# design.net
KiCad netlist of a schematic drawn in Altium Designer
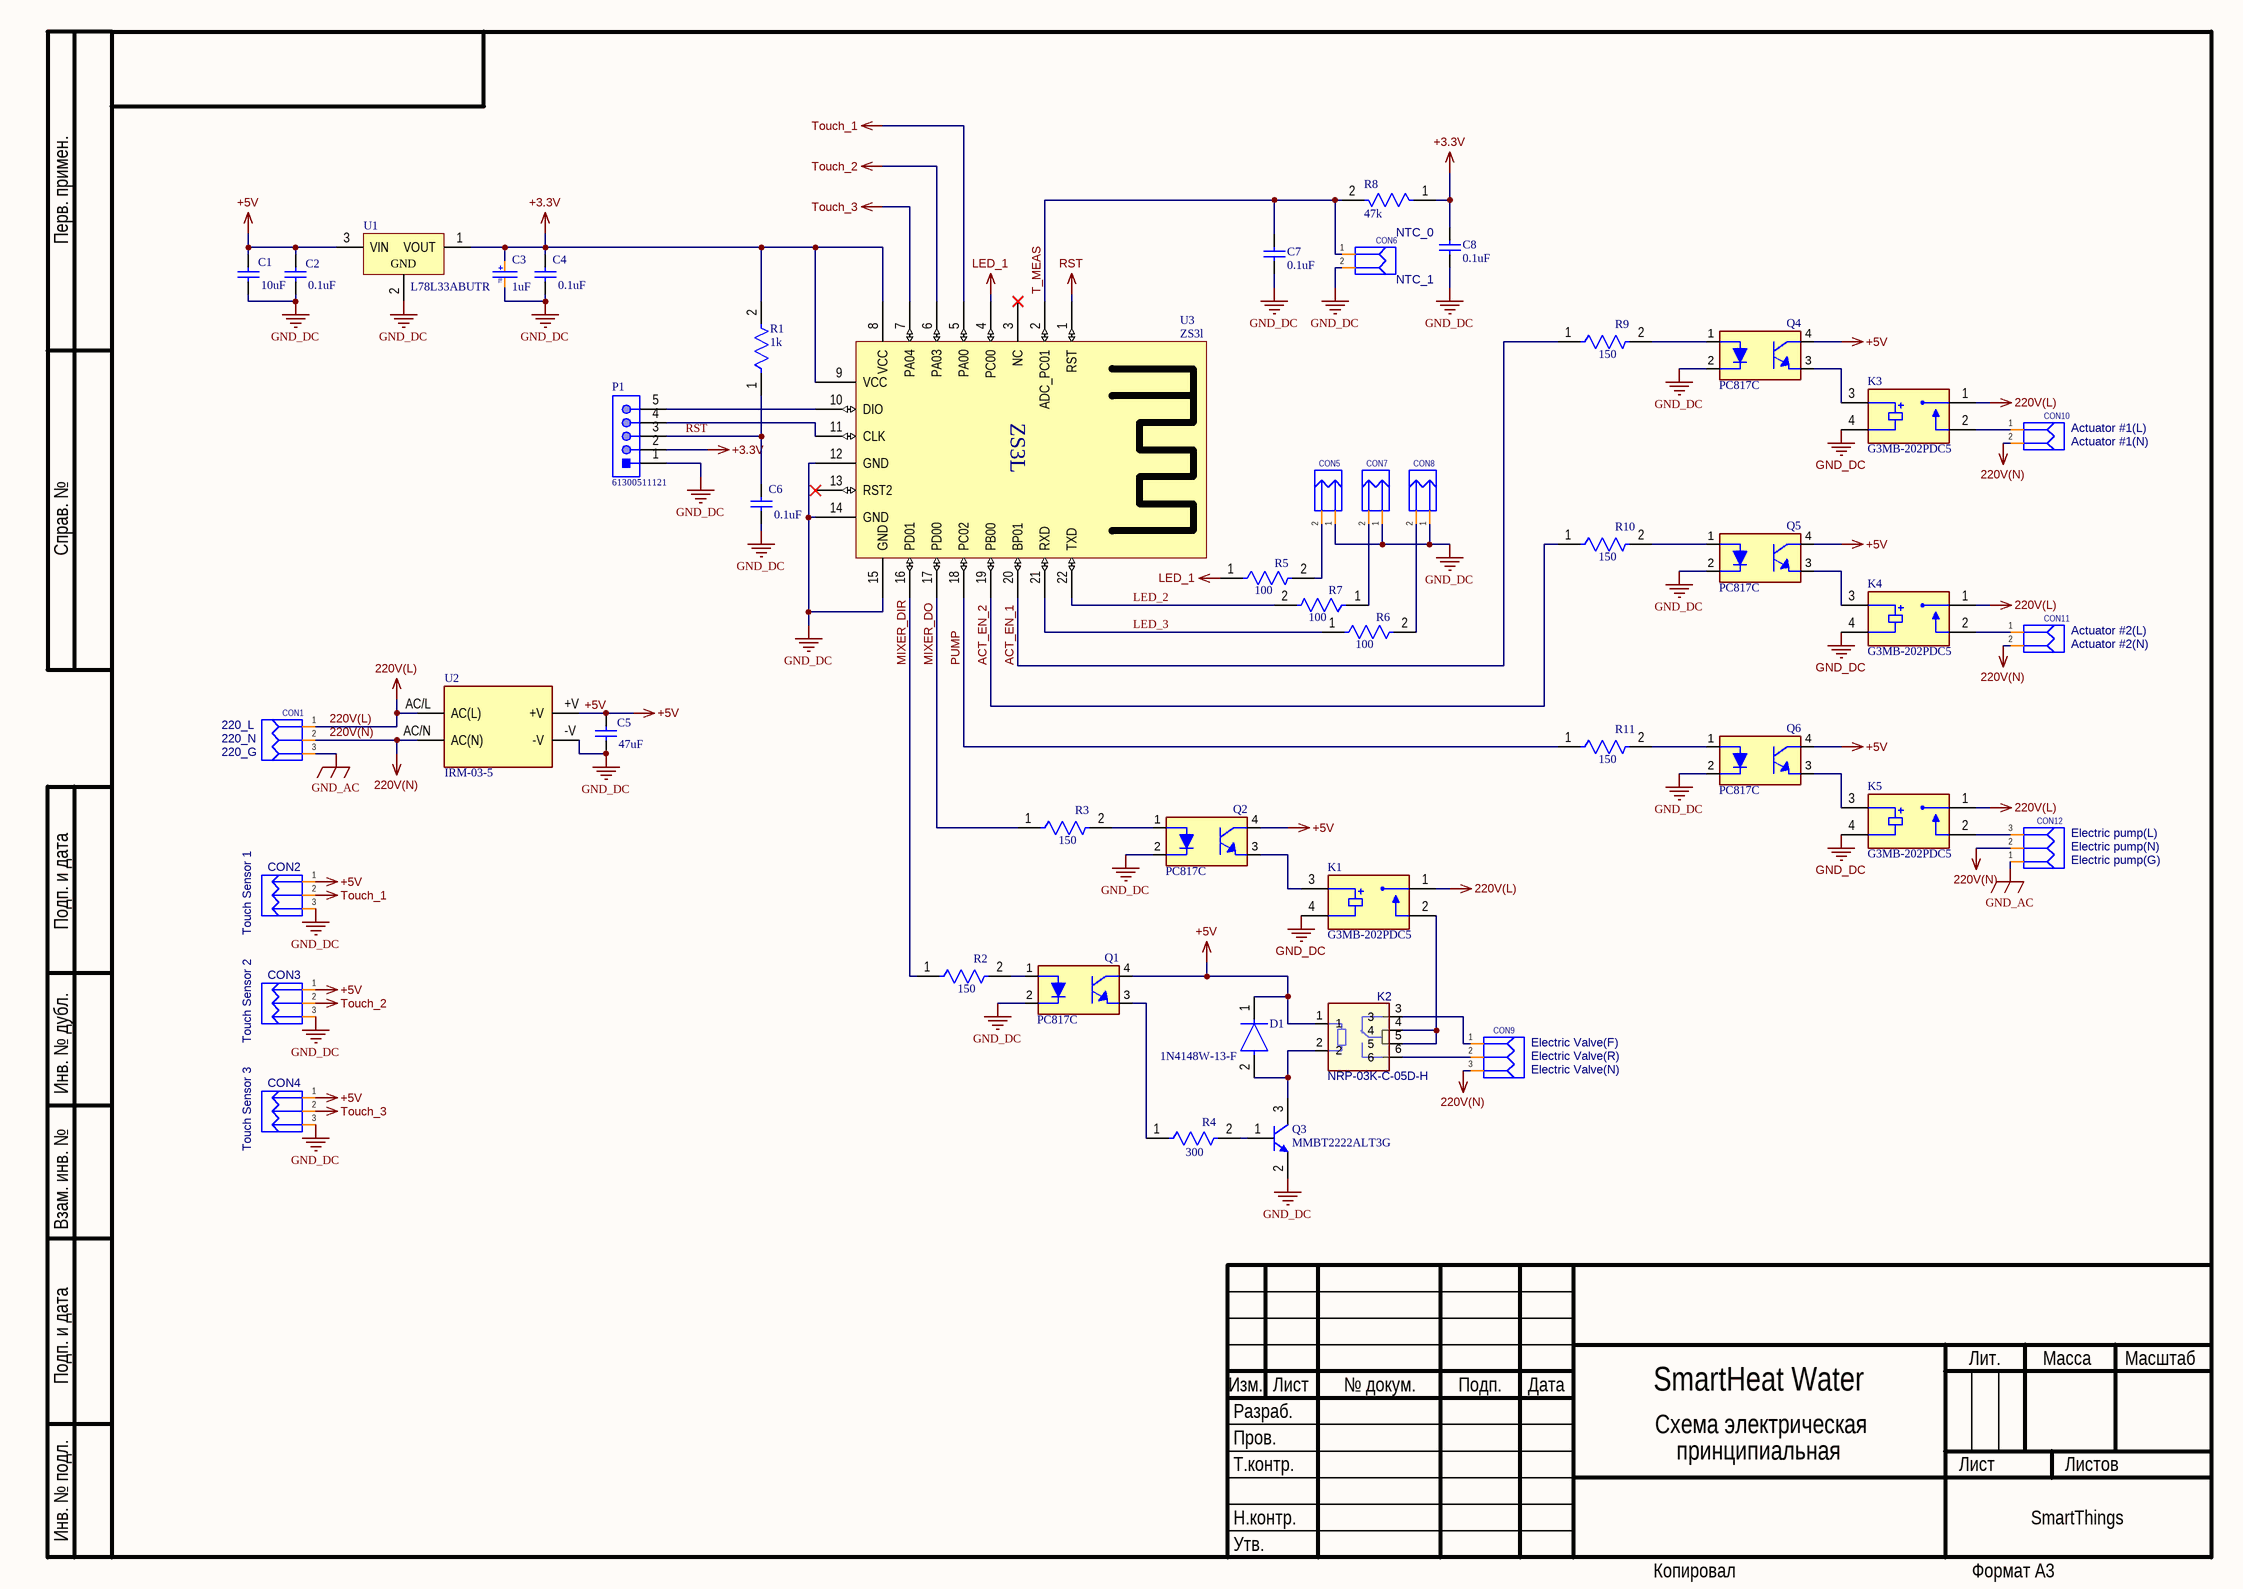
[diagram p0: Схема принципиальная.SchDoc]

(export (version "E")
  (design (tool "Eeschema 10.0.6"))
  (components
    (comp (ref "C1")
      (value "10uF")
      (footprint "CAPC2013X135X45ML10T25")
      (description "GRM21BR61E106KA73L\r\n10uF, +/- 10%, 25 V, 0805")
      (fields (field (name "MANUFACTURER") "Murata"))
      (libsource (lib "Altium Content Vault") (part "CAP-NP-2"))
    )
    (comp (ref "C2")
      (value "0.1uF")
      (footprint "CAPC2013X140X45NL15T25")
      (description "GRM21BR71H104K\r\n0.1 мкФ X7R 10% 50В 0805")
      (fields (field (name "PART NUMBER") "GRM21BR71C475KA73L") (field (name "MANUFACTURER") "Murata"))
      (libsource (lib "Altium Content Vault") (part "CAP"))
    )
    (comp (ref "C3")
      (value "1uF")
      (footprint "TANTAL_B")
      (description "TANTAL TECAP1/50V B, 10%")
      (fields (field (name "PUBLISHER") "Catcatcat Electronics"))
      (libsource (lib "CapacitorElectrolytic") (part "_TANTAL-B"))
    )
    (comp (ref "C4")
      (value "0.1uF")
      (footprint "CAPC2013X140X45NL15T25")
      (description "GRM21BR71H104K\r\n0.1 мкФ X7R 10% 50В 0805")
      (fields (field (name "PART NUMBER") "GRM21BR71C475KA73L") (field (name "MANUFACTURER") "Murata"))
      (libsource (lib "Altium Content Vault") (part "CAP"))
    )
    (comp (ref "C5")
      (value "47uF")
      (footprint "MURA-1210_H_2.7_L")
      (description "Cap Ceramic, 47 uF, +/- 10%, -55 to 85 degC, 2-Pin SMD (1210), RoHS, Tape and Reel")
      (fields (field (name "TOLERANCE") "±10%") (field (name "MANUFACTURER") "Murata"))
      (libsource (lib "Altium Content Vault") (part "CAP-NP-2"))
    )
    (comp (ref "C6")
      (value "0.1uF")
      (footprint "CAPC2013X140X45NL15T25")
      (description "GRM21BR71H104K\r\n0.1 мкФ X7R 10% 50В 0805")
      (fields (field (name "PART NUMBER") "GRM21BR71C475KA73L") (field (name "MANUFACTURER") "Murata"))
      (libsource (lib "Altium Content Vault") (part "CAP"))
    )
    (comp (ref "C7")
      (value "0.1uF")
      (footprint "CAPC2013X140X45NL15T25")
      (description "GRM21BR71H104K\r\n0.1 мкФ X7R 10% 50В 0805")
      (fields (field (name "PART NUMBER") "GRM21BR71C475KA73L") (field (name "MANUFACTURER") "Murata"))
      (libsource (lib "Altium Content Vault") (part "CAP"))
    )
    (comp (ref "C8")
      (value "0.1uF")
      (footprint "CAPC2013X140X45NL15T25")
      (description "GRM21BR71H104K\r\n0.1 мкФ X7R 10% 50В 0805")
      (fields (field (name "PART NUMBER") "GRM21BR71C475KA73L") (field (name "MANUFACTURER") "Murata"))
      (libsource (lib "Altium Content Vault") (part "CAP"))
    )
    (comp (ref "CON1")
      (value "DG129-5.08-3")
      (footprint "DG129-5.08-3")
      (fields (field (name "PUBLISHER") "Catcatcat Electronics"))
      (libsource (lib "Connectors") (part "DG129-5.08-3"))
    )
    (comp (ref "CON2")
      (value "PLS-03")
      (footprint "PLS-03")
      (description "2.54 mm")
      (fields (field (name "PUBLISHER") "Catcatcat Electronics"))
      (libsource (lib "Connectors") (part "PLS-03"))
    )
    (comp (ref "CON3")
      (value "PLS-03")
      (footprint "PLS-03")
      (description "2.54 mm")
      (fields (field (name "PUBLISHER") "Catcatcat Electronics"))
      (libsource (lib "Connectors") (part "PLS-03"))
    )
    (comp (ref "CON4")
      (value "PLS-03")
      (footprint "PLS-03")
      (description "2.54 mm")
      (fields (field (name "PUBLISHER") "Catcatcat Electronics"))
      (libsource (lib "Connectors") (part "PLS-03"))
    )
    (comp (ref "CON5")
      (value "PLS-02")
      (footprint "PLS-02")
      (description "2.54 mm")
      (fields (field (name "PUBLISHER") "Catcatcat Electronics"))
      (libsource (lib "Connectors") (part "PLS-02"))
    )
    (comp (ref "CON6")
      (value "DG129-5.08-2")
      (footprint "DG129-5.08-2")
      (fields (field (name "PUBLISHER") "Catcatcat Electronics"))
      (libsource (lib "Connectors") (part "DG129-5.08-2"))
    )
    (comp (ref "CON7")
      (value "PLS-02")
      (footprint "PLS-02")
      (description "2.54 mm")
      (fields (field (name "PUBLISHER") "Catcatcat Electronics"))
      (libsource (lib "Connectors") (part "PLS-02"))
    )
    (comp (ref "CON8")
      (value "PLS-02")
      (footprint "PLS-02")
      (description "2.54 mm")
      (fields (field (name "PUBLISHER") "Catcatcat Electronics"))
      (libsource (lib "Connectors") (part "PLS-02"))
    )
    (comp (ref "CON9")
      (value "DG129-5.08-3")
      (footprint "DG129-5.08-3")
      (fields (field (name "PUBLISHER") "Catcatcat Electronics"))
      (libsource (lib "Connectors") (part "DG129-5.08-3"))
    )
    (comp (ref "CON10")
      (value "DG129-5.08-2")
      (footprint "DG129-5.08-2")
      (fields (field (name "PUBLISHER") "Catcatcat Electronics"))
      (libsource (lib "Connectors") (part "DG129-5.08-2"))
    )
    (comp (ref "CON11")
      (value "DG129-5.08-2")
      (footprint "DG129-5.08-2")
      (fields (field (name "PUBLISHER") "Catcatcat Electronics"))
      (libsource (lib "Connectors") (part "DG129-5.08-2"))
    )
    (comp (ref "CON12")
      (value "DG129-5.08-3")
      (footprint "DG129-5.08-3")
      (fields (field (name "PUBLISHER") "Catcatcat Electronics"))
      (libsource (lib "Connectors") (part "DG129-5.08-3"))
    )
    (comp (ref "D1")
      (value "1N4148W-13-F")
      (footprint "FP-SOD123-MFG")
      (description "DIODE GEN PURP 100V 150MA SOD123")
      (fields
        (field (name "OCTOPART") "https://octopart.com/1n4148w-13-f-diodes+inc.-2359612")
        (field (name "MANUFACTURER") "Diodes Inc.")
      )
      (libsource (lib "Altium Content Vault") (part "d7152d700b627762746794eb795d46e"))
    )
    (comp (ref "K1")
      (value "G3MB-202PDC5")
      (footprint "G3MB202PDC5:RELAY_G3MB-202PDC5")
      (fields (field (name "MF") "{'manufacturer': u'Omron Automation'}"))
      (libsource (lib "G3MB202PDC5") (part "G3MB-202PDC5"))
    )
    (comp (ref "K2")
      (value "NRP-03K-C-05D-H")
      (footprint "NRP-03K-C-05D-H")
      (libsource (lib "NRP-03K-C-05D-H") (part "NRP-03K-C-05D-H"))
    )
    (comp (ref "K3")
      (value "G3MB-202PDC5")
      (footprint "G3MB202PDC5:RELAY_G3MB-202PDC5")
      (fields (field (name "MF") "{'manufacturer': u'Omron Automation'}"))
      (libsource (lib "G3MB202PDC5") (part "G3MB-202PDC5"))
    )
    (comp (ref "K4")
      (value "G3MB-202PDC5")
      (footprint "G3MB202PDC5:RELAY_G3MB-202PDC5")
      (fields (field (name "MF") "{'manufacturer': u'Omron Automation'}"))
      (libsource (lib "G3MB202PDC5") (part "G3MB-202PDC5"))
    )
    (comp (ref "K5")
      (value "G3MB-202PDC5")
      (footprint "G3MB202PDC5:RELAY_G3MB-202PDC5")
      (fields (field (name "MF") "{'manufacturer': u'Omron Automation'}"))
      (libsource (lib "G3MB202PDC5") (part "G3MB-202PDC5"))
    )
    (comp (ref "P1")
      (value "61300511121")
      (footprint "61300511121")
      (description "THT Vertical Pin Header WR-PHD, Pitch 2.54 mm, Single Row, 5 pins")
      (fields (field (name "MANUFACTURER") "Wurth Elektronik") (field (name "PUBLISHER") "WurthElektronik"))
      (libsource (lib "5pin_conn") (part "CMP-1502-01068-1"))
    )
    (comp (ref "Q1")
      (value "PC817C")
      (footprint "PC817C:DIP762W50P254L650H458Q4B")
      (description "High Density Mounting Type Photocoupler")
      (fields (field (name "MF") "{'manufacturer': u'Taiwan Semiconductor'}"))
      (libsource (lib "PC817C") (part "PC817C"))
    )
    (comp (ref "Q2")
      (value "PC817C")
      (footprint "PC817C:DIP762W50P254L650H458Q4B")
      (description "High Density Mounting Type Photocoupler")
      (fields (field (name "MF") "{'manufacturer': u'Taiwan Semiconductor'}"))
      (libsource (lib "PC817C") (part "PC817C"))
    )
    (comp (ref "Q3")
      (value "MMBT2222ALT3G")
      (footprint "ONSC-SOT-23-3-318-08_V")
      (description "General Purpose Transistor, NPN Silicon, 3-Pin SOT-23, Pb-Free, Tape and Reel")
      (fields (field (name "MANUFACTURER") "On Semiconductor"))
      (libsource (lib "Altium Content Vault") (part "ONSC-NPN-B1E2C3-3"))
    )
    (comp (ref "Q4")
      (value "PC817C")
      (footprint "PC817C:DIP762W50P254L650H458Q4B")
      (description "High Density Mounting Type Photocoupler")
      (fields (field (name "MF") "{'manufacturer': u'Taiwan Semiconductor'}"))
      (libsource (lib "PC817C") (part "PC817C"))
    )
    (comp (ref "Q5")
      (value "PC817C")
      (footprint "PC817C:DIP762W50P254L650H458Q4B")
      (description "High Density Mounting Type Photocoupler")
      (fields (field (name "MF") "{'manufacturer': u'Taiwan Semiconductor'}"))
      (libsource (lib "PC817C") (part "PC817C"))
    )
    (comp (ref "Q6")
      (value "PC817C")
      (footprint "PC817C:DIP762W50P254L650H458Q4B")
      (description "High Density Mounting Type Photocoupler")
      (fields (field (name "MF") "{'manufacturer': u'Taiwan Semiconductor'}"))
      (libsource (lib "PC817C") (part "PC817C"))
    )
    (comp (ref "R1")
      (value "1k")
      (footprint "FP-CR0805-IPC_C")
      (description "0805 150Ω 0.125W 1%")
      (fields (field (name "TOLERANCE") "1%"))
      (libsource (lib "Altium Content Vault") (part "1029c3af85768c4190bb7ad29bc67b5"))
    )
    (comp (ref "R2")
      (value "150")
      (footprint "FP-CR0805-IPC_C")
      (description "0805 150Ω 0.125W 1%")
      (fields (field (name "TOLERANCE") "1%"))
      (libsource (lib "Altium Content Vault") (part "1029c3af85768c4190bb7ad29bc67b5"))
    )
    (comp (ref "R3")
      (value "150")
      (footprint "FP-CR0805-IPC_C")
      (description "0805 150Ω 0.125W 1%")
      (fields (field (name "TOLERANCE") "1%"))
      (libsource (lib "Altium Content Vault") (part "1029c3af85768c4190bb7ad29bc67b5"))
    )
    (comp (ref "R4")
      (value "300")
      (footprint "FP-CR0805-IPC_C")
      (description "0805 300kΩ 0.125W 1%")
      (fields (field (name "TOLERANCE") "1%"))
      (libsource (lib "Altium Content Vault") (part "1029c3af85768c4190bb7ad29bc67b5"))
    )
    (comp (ref "R5")
      (value "100")
      (footprint "FP-CR0805-IPC_C")
      (description "0805 150Ω 0.125W 1%")
      (fields (field (name "TOLERANCE") "1%"))
      (libsource (lib "Altium Content Vault") (part "1029c3af85768c4190bb7ad29bc67b5"))
    )
    (comp (ref "R6")
      (value "100")
      (footprint "FP-CR0805-IPC_C")
      (description "0805 150Ω 0.125W 1%")
      (fields (field (name "TOLERANCE") "1%"))
      (libsource (lib "Altium Content Vault") (part "1029c3af85768c4190bb7ad29bc67b5"))
    )
    (comp (ref "R7")
      (value "100")
      (footprint "FP-CR0805-IPC_C")
      (description "0805 150Ω 0.125W 1%")
      (fields (field (name "TOLERANCE") "1%"))
      (libsource (lib "Altium Content Vault") (part "1029c3af85768c4190bb7ad29bc67b5"))
    )
    (comp (ref "R8")
      (value "47k")
      (footprint "FP-CRCW1206-e3-IPC_C")
      (description "10kΩ, 1%, 0.25W 1206")
      (fields (field (name "TOLERANCE") "1%"))
      (libsource (lib "Altium Content Vault") (part "1029c3af85768c4190bb7ad29bc67b5"))
    )
    (comp (ref "R9")
      (value "150")
      (footprint "FP-CR0805-IPC_C")
      (description "0805 150Ω 0.125W 1%")
      (fields (field (name "TOLERANCE") "1%"))
      (libsource (lib "Altium Content Vault") (part "1029c3af85768c4190bb7ad29bc67b5"))
    )
    (comp (ref "R10")
      (value "150")
      (footprint "FP-CR0805-IPC_C")
      (description "0805 150Ω 0.125W 1%")
      (fields (field (name "TOLERANCE") "1%"))
      (libsource (lib "Altium Content Vault") (part "1029c3af85768c4190bb7ad29bc67b5"))
    )
    (comp (ref "R11")
      (value "150")
      (footprint "FP-CR0805-IPC_C")
      (description "0805 150Ω 0.125W 1%")
      (fields (field (name "TOLERANCE") "1%"))
      (libsource (lib "Altium Content Vault") (part "1029c3af85768c4190bb7ad29bc67b5"))
    )
    (comp (ref "U1")
      (value "L78L33ABUTR")
      (footprint "SOT-89_L")
      (libsource (lib "L78L33ABUTR") (part "CMP-0244-00410-1"))
    )
    (comp (ref "U2")
      (value "IRM-03-5")
      (footprint "footprint_IRM-03-5")
      (description "AC-DC Single output Encapsulated power supply; Output 5Vdc at 0.6A; PCB mount, miniature size")
      (fields (field (name "MF") "{'manufacturer': u'MEAN WELL'}"))
      (libsource (lib "IRM-03-5") (part "IRM-03-5"))
    )
    (comp (ref "U3")
      (value "ZS3l")
      (footprint "zs3l")
      (description "ZS3L module on chip EFR32MG21A020F768IM32")
      (libsource (lib "zs3l") (part "ZS3l"))
    )
  )
  (nets
    (net (code "1") (name "+3.3V") (class "Default")
      (node (ref "C3") (pin "1") (pintype "passive"))
      (node (ref "C4") (pin "2") (pinfunction "2_2") (pintype "passive"))
      (node (ref "C8") (pin "2") (pinfunction "2_2") (pintype "passive"))
      (node (ref "P1") (pin "2") (pinfunction "2_2") (pintype "passive"))
      (node (ref "R1") (pin "2") (pinfunction "2_2") (pintype "passive"))
      (node (ref "R8") (pin "1") (pinfunction "1_1") (pintype "passive"))
      (node (ref "U1") (pin "1") (pinfunction "VOUT_1") (pintype "power_in"))
      (node (ref "U3") (pin "8") (pinfunction "VCC_8") (pintype "power_in"))
      (node (ref "U3") (pin "9") (pinfunction "VCC_9") (pintype "power_in"))
    )
    (net (code "2") (name "+5V") (class "Default")
      (node (ref "C1") (pin "2") (pinfunction "2_2") (pintype "passive"))
      (node (ref "C2") (pin "2") (pinfunction "2_2") (pintype "passive"))
      (node (ref "C5") (pin "2") (pinfunction "2_2") (pintype "passive"))
      (node (ref "CON2") (pin "1") (pinfunction "1_1") (pintype "passive"))
      (node (ref "CON3") (pin "1") (pinfunction "1_1") (pintype "passive"))
      (node (ref "CON4") (pin "1") (pinfunction "1_1") (pintype "passive"))
      (node (ref "D1") (pin "1") (pinfunction "C_1") (pintype "passive"))
      (node (ref "K2") (pin "1") (pinfunction "1_1") (pintype "passive"))
      (node (ref "Q1") (pin "4") (pinfunction "4_4") (pintype "passive"))
      (node (ref "Q2") (pin "4") (pinfunction "4_4") (pintype "passive"))
      (node (ref "Q4") (pin "4") (pinfunction "4_4") (pintype "passive"))
      (node (ref "Q5") (pin "4") (pinfunction "4_4") (pintype "passive"))
      (node (ref "Q6") (pin "4") (pinfunction "4_4") (pintype "passive"))
      (node (ref "U1") (pin "3") (pinfunction "VIN_3") (pintype "power_in"))
      (node (ref "U2") (pin "+V") (pinfunction "+V_+V") (pintype "power_in"))
    )
    (net (code "3") (name "/ACT_EN_1") (class "Default")
      (node (ref "R9") (pin "1") (pinfunction "1_1") (pintype "passive"))
      (node (ref "U3") (pin "20") (pinfunction "BP01_20") (pintype "bidirectional"))
    )
    (net (code "4") (name "/ACT_EN_2") (class "Default")
      (node (ref "R10") (pin "1") (pinfunction "1_1") (pintype "passive"))
      (node (ref "U3") (pin "19") (pinfunction "PB00_19") (pintype "bidirectional"))
    )
    (net (code "5") (name "/LED_2") (class "Default")
      (node (ref "R7") (pin "2") (pinfunction "2_2") (pintype "passive"))
      (node (ref "U3") (pin "22") (pinfunction "TXD_22") (pintype "bidirectional"))
    )
    (net (code "6") (name "/LED_3") (class "Default")
      (node (ref "R6") (pin "1") (pinfunction "1_1") (pintype "passive"))
      (node (ref "U3") (pin "21") (pinfunction "RXD_21") (pintype "bidirectional"))
    )
    (net (code "7") (name "/MIXER_DIR") (class "Default")
      (node (ref "R2") (pin "1") (pinfunction "1_1") (pintype "passive"))
      (node (ref "U3") (pin "16") (pinfunction "PD01_16") (pintype "bidirectional"))
    )
    (net (code "8") (name "/MIXER_DO") (class "Default")
      (node (ref "R3") (pin "1") (pinfunction "1_1") (pintype "passive"))
      (node (ref "U3") (pin "17") (pinfunction "PD00_17") (pintype "bidirectional"))
    )
    (net (code "9") (name "/PUMP") (class "Default")
      (node (ref "R11") (pin "1") (pinfunction "1_1") (pintype "passive"))
      (node (ref "U3") (pin "18") (pinfunction "PC02_18") (pintype "bidirectional"))
    )
    (net (code "10") (name "/T_MEAS") (class "Default")
      (node (ref "C7") (pin "2") (pinfunction "2_2") (pintype "passive"))
      (node (ref "CON6") (pin "1") (pinfunction "1_1") (pintype "passive"))
      (node (ref "R8") (pin "2") (pinfunction "2_2") (pintype "passive"))
      (node (ref "U3") (pin "2") (pinfunction "ADC_PC01_2") (pintype "bidirectional"))
    )
    (net (code "11") (name "220V(L)") (class "Default")
      (node (ref "CON1") (pin "1") (pinfunction "1_1") (pintype "passive"))
      (node (ref "K1") (pin "1") (pinfunction "1_1") (pintype "passive"))
      (node (ref "K3") (pin "1") (pinfunction "1_1") (pintype "passive"))
      (node (ref "K4") (pin "1") (pinfunction "1_1") (pintype "passive"))
      (node (ref "K5") (pin "1") (pinfunction "1_1") (pintype "passive"))
      (node (ref "U2") (pin "AC/L") (pinfunction "AC(L)_AC/L") (pintype "power_in"))
    )
    (net (code "12") (name "220V(N)") (class "Default")
      (node (ref "CON1") (pin "2") (pinfunction "2_2") (pintype "passive"))
      (node (ref "CON10") (pin "2") (pinfunction "2_2") (pintype "passive"))
      (node (ref "CON11") (pin "2") (pinfunction "2_2") (pintype "passive"))
      (node (ref "CON12") (pin "2") (pinfunction "2_2") (pintype "passive"))
      (node (ref "CON9") (pin "3") (pinfunction "3_3") (pintype "passive"))
      (node (ref "U2") (pin "AC/N") (pinfunction "AC(N)_AC/N") (pintype "power_in"))
    )
    (net (code "13") (name "GND_AC") (class "Default")
      (node (ref "CON1") (pin "3") (pinfunction "3_3") (pintype "passive"))
      (node (ref "CON12") (pin "1") (pinfunction "1_1") (pintype "passive"))
    )
    (net (code "14") (name "GND_DC") (class "Default")
      (node (ref "C1") (pin "1") (pinfunction "1_1") (pintype "passive"))
      (node (ref "C2") (pin "1") (pinfunction "1_1") (pintype "passive"))
      (node (ref "C3") (pin "2") (pintype "passive"))
      (node (ref "C4") (pin "1") (pinfunction "1_1") (pintype "passive"))
      (node (ref "C5") (pin "1") (pinfunction "1_1") (pintype "passive"))
      (node (ref "C6") (pin "1") (pinfunction "1_1") (pintype "passive"))
      (node (ref "C7") (pin "1") (pinfunction "1_1") (pintype "passive"))
      (node (ref "C8") (pin "1") (pinfunction "1_1") (pintype "passive"))
      (node (ref "CON2") (pin "3") (pinfunction "3_3") (pintype "passive"))
      (node (ref "CON3") (pin "3") (pinfunction "3_3") (pintype "passive"))
      (node (ref "CON4") (pin "3") (pinfunction "3_3") (pintype "passive"))
      (node (ref "CON5") (pin "1") (pinfunction "1_1") (pintype "passive"))
      (node (ref "CON6") (pin "2") (pinfunction "2_2") (pintype "passive"))
      (node (ref "CON7") (pin "1") (pinfunction "1_1") (pintype "passive"))
      (node (ref "CON8") (pin "1") (pinfunction "1_1") (pintype "passive"))
      (node (ref "K1") (pin "4") (pinfunction "4_4") (pintype "passive"))
      (node (ref "K3") (pin "4") (pinfunction "4_4") (pintype "passive"))
      (node (ref "K4") (pin "4") (pinfunction "4_4") (pintype "passive"))
      (node (ref "K5") (pin "4") (pinfunction "4_4") (pintype "passive"))
      (node (ref "P1") (pin "1") (pinfunction "1_1") (pintype "passive"))
      (node (ref "Q1") (pin "2") (pinfunction "2_2") (pintype "passive"))
      (node (ref "Q2") (pin "2") (pinfunction "2_2") (pintype "passive"))
      (node (ref "Q3") (pin "2") (pinfunction "E_2") (pintype "passive"))
      (node (ref "Q4") (pin "2") (pinfunction "2_2") (pintype "passive"))
      (node (ref "Q5") (pin "2") (pinfunction "2_2") (pintype "passive"))
      (node (ref "Q6") (pin "2") (pinfunction "2_2") (pintype "passive"))
      (node (ref "U1") (pin "2") (pinfunction "GND_2") (pintype "power_in"))
      (node (ref "U2") (pin "-V") (pinfunction "-V_-V") (pintype "power_in"))
      (node (ref "U3") (pin "12") (pinfunction "GND_12") (pintype "power_in"))
      (node (ref "U3") (pin "14") (pinfunction "GND_14") (pintype "power_in"))
      (node (ref "U3") (pin "15") (pinfunction "GND_15") (pintype "power_in"))
    )
    (net (code "15") (name "LED_1") (class "Default")
      (node (ref "R5") (pin "1") (pinfunction "1_1") (pintype "passive"))
      (node (ref "U3") (pin "4") (pinfunction "PC00_4") (pintype "bidirectional"))
    )
    (net (code "16") (name "Net-(CON5-Pad2)") (class "Default")
      (node (ref "CON5") (pin "2") (pinfunction "2_2") (pintype "passive"))
      (node (ref "R5") (pin "2") (pinfunction "2_2") (pintype "passive"))
    )
    (net (code "17") (name "Net-(CON7-Pad2)") (class "Default")
      (node (ref "CON7") (pin "2") (pinfunction "2_2") (pintype "passive"))
      (node (ref "R7") (pin "1") (pinfunction "1_1") (pintype "passive"))
    )
    (net (code "18") (name "Net-(CON8-Pad2)") (class "Default")
      (node (ref "CON8") (pin "2") (pinfunction "2_2") (pintype "passive"))
      (node (ref "R6") (pin "2") (pinfunction "2_2") (pintype "passive"))
    )
    (net (code "19") (name "Net-(CON9-Pad1)") (class "Default")
      (node (ref "CON9") (pin "1") (pinfunction "1_1") (pintype "passive"))
      (node (ref "K2") (pin "3") (pinfunction "3_3") (pintype "passive"))
    )
    (net (code "20") (name "Net-(CON9-Pad2)") (class "Default")
      (node (ref "CON9") (pin "2") (pinfunction "2_2") (pintype "passive"))
      (node (ref "K2") (pin "6") (pinfunction "6_6") (pintype "passive"))
    )
    (net (code "21") (name "Net-(CON10-Pad1)") (class "Default")
      (node (ref "CON10") (pin "1") (pinfunction "1_1") (pintype "passive"))
      (node (ref "K3") (pin "2") (pinfunction "2_2") (pintype "passive"))
    )
    (net (code "22") (name "Net-(CON11-Pad1)") (class "Default")
      (node (ref "CON11") (pin "1") (pinfunction "1_1") (pintype "passive"))
      (node (ref "K4") (pin "2") (pinfunction "2_2") (pintype "passive"))
    )
    (net (code "23") (name "Net-(CON12-Pad3)") (class "Default")
      (node (ref "CON12") (pin "3") (pinfunction "3_3") (pintype "passive"))
      (node (ref "K5") (pin "2") (pinfunction "2_2") (pintype "passive"))
    )
    (net (code "24") (name "Net-(D1-A)") (class "Default")
      (node (ref "D1") (pin "2") (pinfunction "A_2") (pintype "passive"))
      (node (ref "K2") (pin "2") (pinfunction "2_2") (pintype "passive"))
      (node (ref "Q3") (pin "3") (pinfunction "C_3") (pintype "passive"))
    )
    (net (code "25") (name "Net-(K1-Pad2)") (class "Default")
      (node (ref "K1") (pin "2") (pinfunction "2_2") (pintype "passive"))
      (node (ref "K2") (pin "4") (pinfunction "4_4") (pintype "passive"))
      (node (ref "K2") (pin "5") (pinfunction "5_5") (pintype "passive"))
    )
    (net (code "26") (name "Net-(K1-Pad3)") (class "Default")
      (node (ref "K1") (pin "3") (pinfunction "3_3") (pintype "passive"))
      (node (ref "Q2") (pin "3") (pinfunction "3_3") (pintype "passive"))
    )
    (net (code "27") (name "Net-(K3-Pad3)") (class "Default")
      (node (ref "K3") (pin "3") (pinfunction "3_3") (pintype "passive"))
      (node (ref "Q4") (pin "3") (pinfunction "3_3") (pintype "passive"))
    )
    (net (code "28") (name "Net-(K4-Pad3)") (class "Default")
      (node (ref "K4") (pin "3") (pinfunction "3_3") (pintype "passive"))
      (node (ref "Q5") (pin "3") (pinfunction "3_3") (pintype "passive"))
    )
    (net (code "29") (name "Net-(K5-Pad3)") (class "Default")
      (node (ref "K5") (pin "3") (pinfunction "3_3") (pintype "passive"))
      (node (ref "Q6") (pin "3") (pinfunction "3_3") (pintype "passive"))
    )
    (net (code "30") (name "Net-(Q1-Pad1)") (class "Default")
      (node (ref "Q1") (pin "1") (pinfunction "1_1") (pintype "passive"))
      (node (ref "R2") (pin "2") (pinfunction "2_2") (pintype "passive"))
    )
    (net (code "31") (name "Net-(Q1-Pad3)") (class "Default")
      (node (ref "Q1") (pin "3") (pinfunction "3_3") (pintype "passive"))
      (node (ref "R4") (pin "1") (pinfunction "1_1") (pintype "passive"))
    )
    (net (code "32") (name "Net-(Q2-Pad1)") (class "Default")
      (node (ref "Q2") (pin "1") (pinfunction "1_1") (pintype "passive"))
      (node (ref "R3") (pin "2") (pinfunction "2_2") (pintype "passive"))
    )
    (net (code "33") (name "Net-(Q3-B)") (class "Default")
      (node (ref "Q3") (pin "1") (pinfunction "B_1") (pintype "passive"))
      (node (ref "R4") (pin "2") (pinfunction "2_2") (pintype "passive"))
    )
    (net (code "34") (name "Net-(Q4-Pad1)") (class "Default")
      (node (ref "Q4") (pin "1") (pinfunction "1_1") (pintype "passive"))
      (node (ref "R9") (pin "2") (pinfunction "2_2") (pintype "passive"))
    )
    (net (code "35") (name "Net-(Q5-Pad1)") (class "Default")
      (node (ref "Q5") (pin "1") (pinfunction "1_1") (pintype "passive"))
      (node (ref "R10") (pin "2") (pinfunction "2_2") (pintype "passive"))
    )
    (net (code "36") (name "Net-(Q6-Pad1)") (class "Default")
      (node (ref "Q6") (pin "1") (pinfunction "1_1") (pintype "passive"))
      (node (ref "R11") (pin "2") (pinfunction "2_2") (pintype "passive"))
    )
    (net (code "37") (name "Net-(U3-CLK)") (class "Default")
      (node (ref "P1") (pin "4") (pinfunction "4_4") (pintype "passive"))
      (node (ref "U3") (pin "11") (pinfunction "CLK_11") (pintype "bidirectional"))
    )
    (net (code "38") (name "Net-(U3-DIO)") (class "Default")
      (node (ref "P1") (pin "5") (pinfunction "5_5") (pintype "passive"))
      (node (ref "U3") (pin "10") (pinfunction "DIO_10") (pintype "bidirectional"))
    )
    (net (code "39") (name "RST") (class "Default")
      (node (ref "C6") (pin "2") (pinfunction "2_2") (pintype "passive"))
      (node (ref "P1") (pin "3") (pinfunction "3_3") (pintype "passive"))
      (node (ref "R1") (pin "1") (pinfunction "1_1") (pintype "passive"))
      (node (ref "U3") (pin "1") (pinfunction "RST_1") (pintype "bidirectional"))
    )
    (net (code "40") (name "Touch_1") (class "Default")
      (node (ref "CON2") (pin "2") (pinfunction "2_2") (pintype "passive"))
      (node (ref "U3") (pin "5") (pinfunction "PA00_5") (pintype "bidirectional"))
    )
    (net (code "41") (name "Touch_2") (class "Default")
      (node (ref "CON3") (pin "2") (pinfunction "2_2") (pintype "passive"))
      (node (ref "U3") (pin "6") (pinfunction "PA03_6") (pintype "bidirectional"))
    )
    (net (code "42") (name "Touch_3") (class "Default")
      (node (ref "CON4") (pin "2") (pinfunction "2_2") (pintype "passive"))
      (node (ref "U3") (pin "7") (pinfunction "PA04_7") (pintype "bidirectional"))
    )
    (net (code "43") (name "unconnected-(U3-NC-Pad3)") (class "Default")
      (node (ref "U3") (pin "3") (pinfunction "NC_3") (pintype "passive+no_connect"))
    )
    (net (code "44") (name "unconnected-(U3-RST2-Pad13)") (class "Default")
      (node (ref "U3") (pin "13") (pinfunction "RST2_13") (pintype "bidirectional+no_connect"))
    )
  )
)
